# megapci3.net
KiCad netlist of a schematic drawn in EAGLE
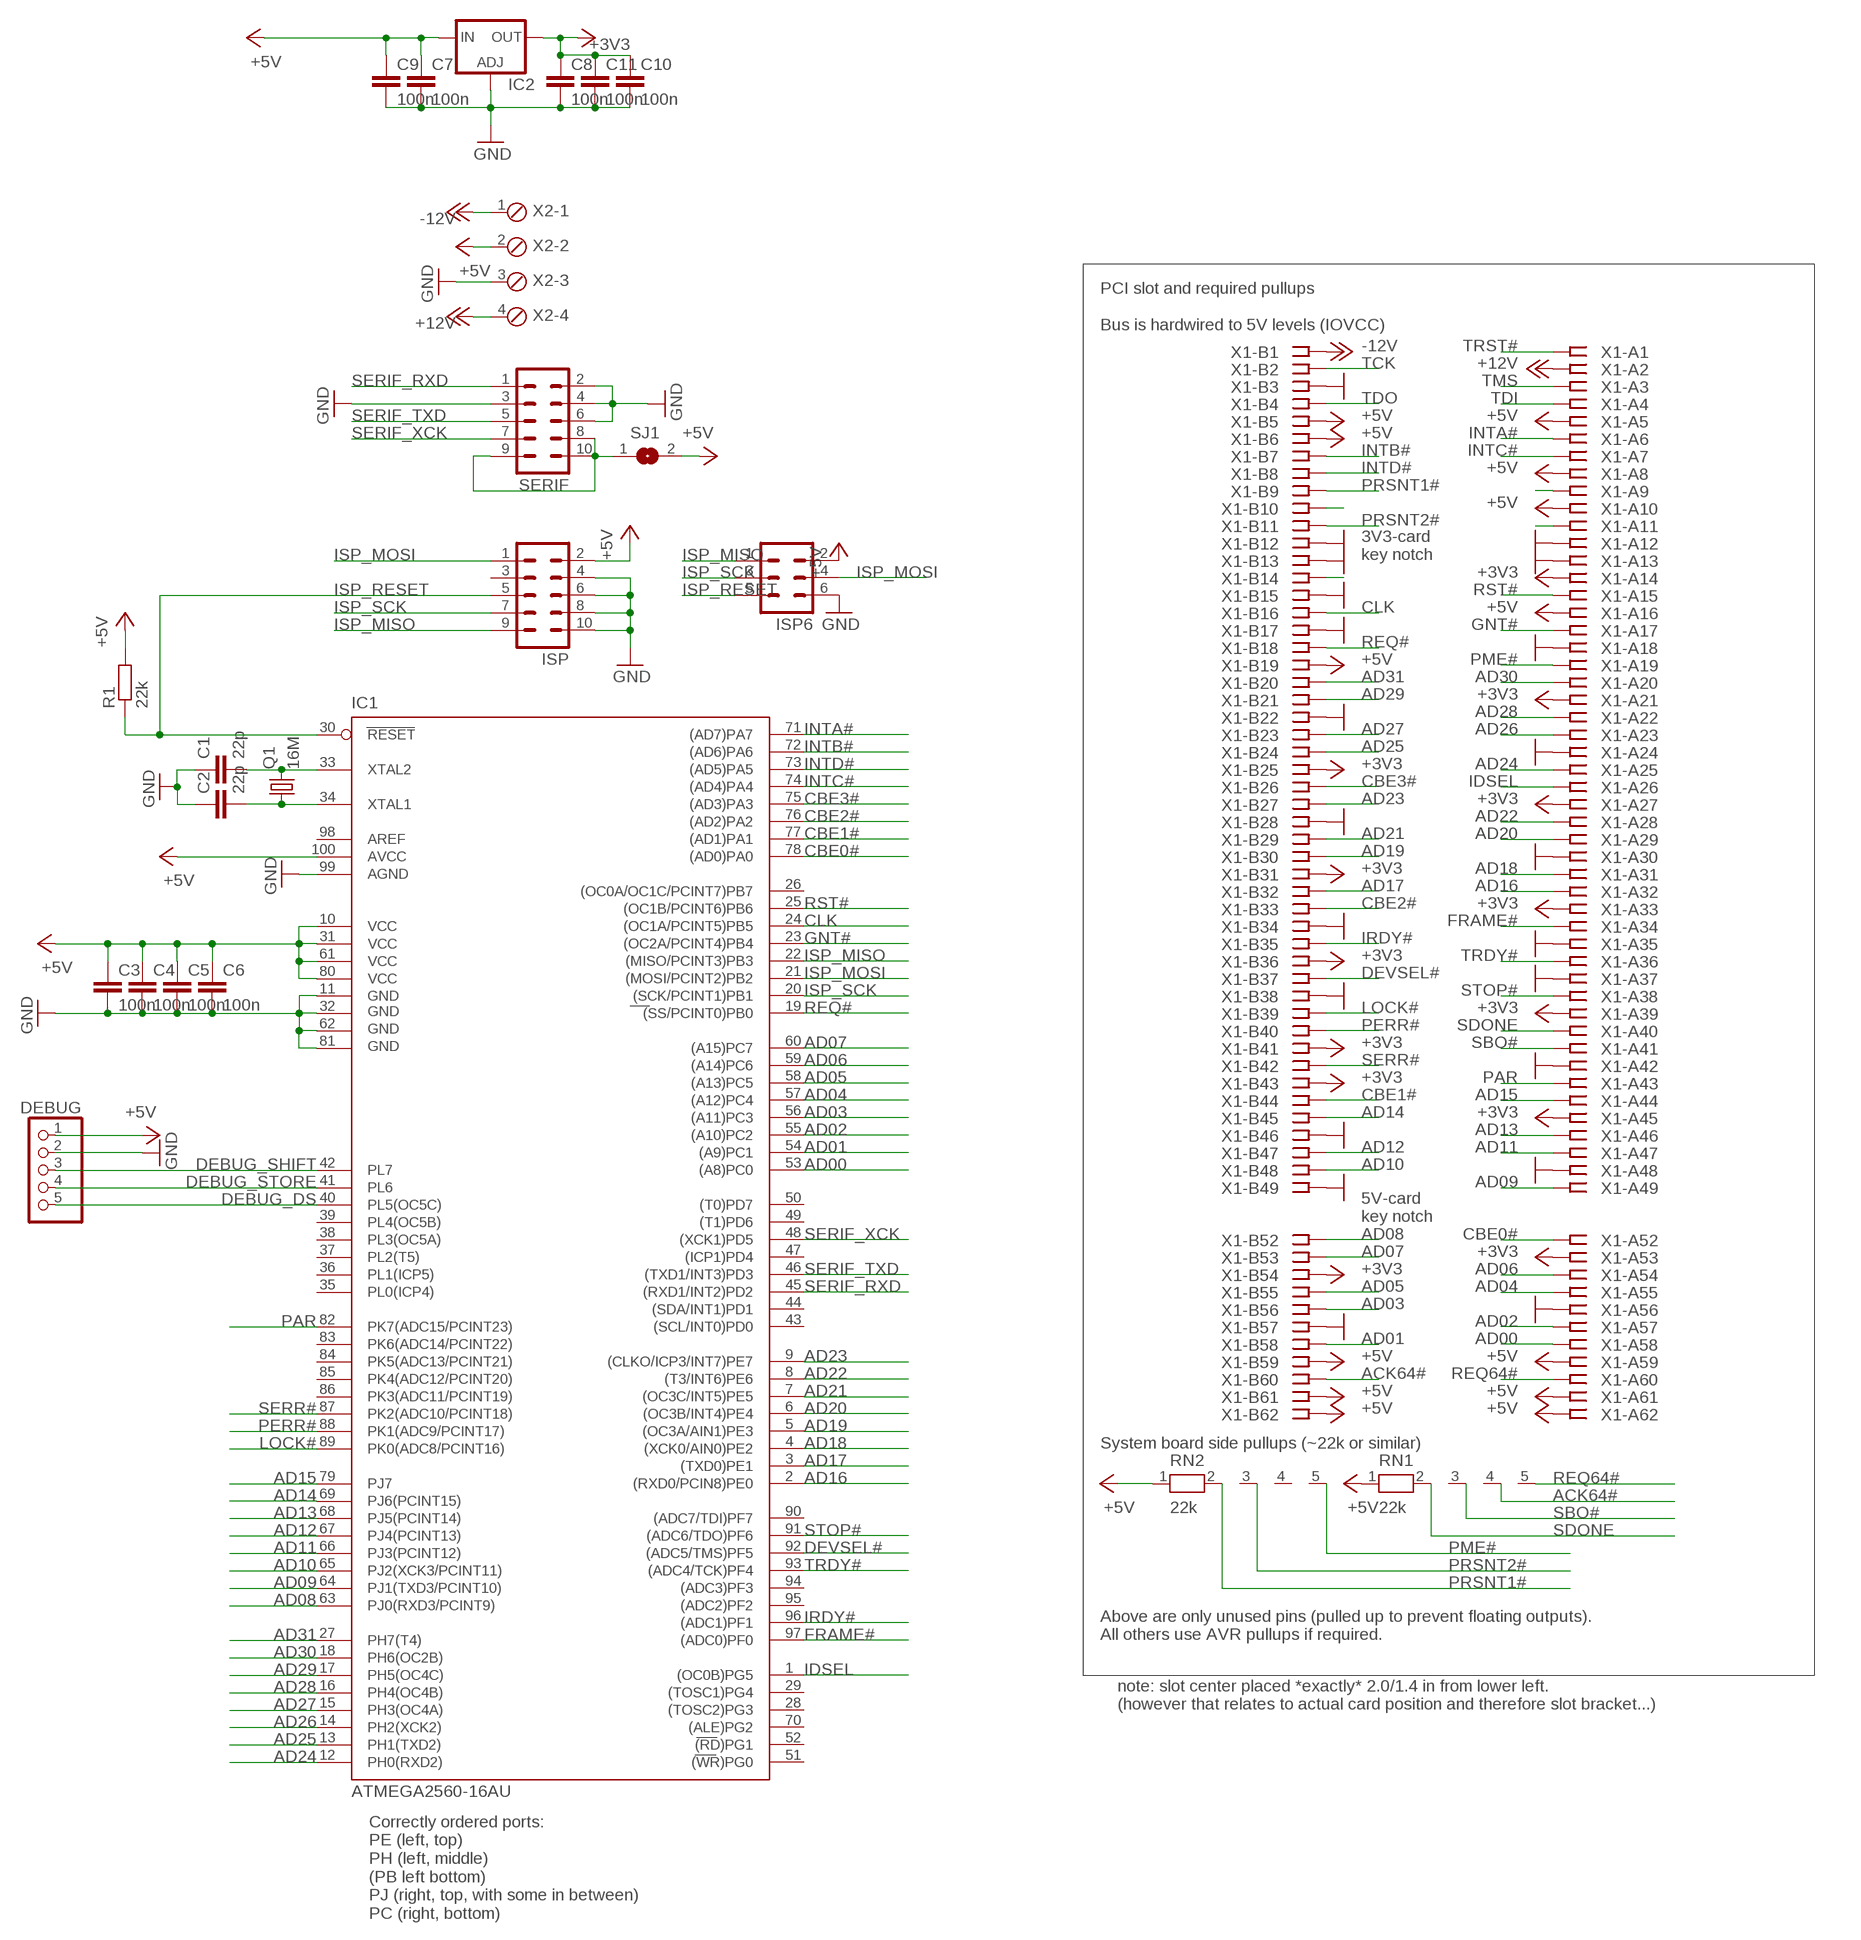
[diagram p0: schematic, sheet 1]

(export (version "E")
  (design (tool "Eeschema 10.0.6"))
  (components
    (comp (ref "C1")
      (value "22p")
      (footprint "eagle-import:C0805")
      (libsource (lib "eagle-import") (part "C-EUC0805"))
    )
    (comp (ref "C2")
      (value "22p")
      (footprint "eagle-import:C0805")
      (libsource (lib "eagle-import") (part "C-EUC0805"))
    )
    (comp (ref "C3")
      (value "100n")
      (footprint "eagle-import:C0805")
      (libsource (lib "eagle-import") (part "C-EUC0805"))
    )
    (comp (ref "C4")
      (value "100n")
      (footprint "eagle-import:C0805")
      (libsource (lib "eagle-import") (part "C-EUC0805"))
    )
    (comp (ref "C5")
      (value "100n")
      (footprint "eagle-import:C0805")
      (libsource (lib "eagle-import") (part "C-EUC0805"))
    )
    (comp (ref "C6")
      (value "100n")
      (footprint "eagle-import:C0805")
      (libsource (lib "eagle-import") (part "C-EUC0805"))
    )
    (comp (ref "C7")
      (value "100n")
      (footprint "eagle-import:C0805")
      (libsource (lib "eagle-import") (part "C-EUC0805"))
    )
    (comp (ref "C8")
      (value "100n")
      (footprint "eagle-import:C0805")
      (libsource (lib "eagle-import") (part "C-EUC0805"))
    )
    (comp (ref "C9")
      (value "100n")
      (footprint "eagle-import:C0805")
      (libsource (lib "eagle-import") (part "C-EUC0805"))
    )
    (comp (ref "C10")
      (value "100n")
      (footprint "eagle-import:C0805")
      (libsource (lib "eagle-import") (part "C-EUC0805"))
    )
    (comp (ref "C11")
      (value "100n")
      (footprint "eagle-import:C0805")
      (libsource (lib "eagle-import") (part "C-EUC0805"))
    )
    (comp (ref "DEBUG")
      (value "PINHD-1X5")
      (footprint "eagle-import:1X05")
      (libsource (lib "eagle-import") (part "PINHD-1X5"))
    )
    (comp (ref "IC1")
      (value "ATMEGA2560-16AU")
      (footprint "eagle-import:TQFP100")
      (libsource (lib "eagle-import") (part "ATMEGAAU2560-16"))
    )
    (comp (ref "IC2")
      (value "LM317TS")
      (footprint "eagle-import:317TS")
      (libsource (lib "eagle-import") (part "LM317TS"))
    )
    (comp (ref "ISP")
      (value "ML10")
      (footprint "eagle-import:ML10")
      (libsource (lib "eagle-import") (part "ML10"))
    )
    (comp (ref "ISP6")
      (value "ML6")
      (footprint "eagle-import:ML6")
      (libsource (lib "eagle-import") (part "ML6"))
    )
    (comp (ref "Q1")
      (value "16M")
      (footprint "eagle-import:HC49_S")
      (libsource (lib "eagle-import") (part "CRYSTALHC49S"))
    )
    (comp (ref "R1")
      (value "22k")
      (footprint "eagle-import:R0805")
      (libsource (lib "eagle-import") (part "R-EU_R0805"))
    )
    (comp (ref "RN1")
      (value "22k")
      (footprint "eagle-import:RN-5")
      (libsource (lib "eagle-import") (part "RN04"))
    )
    (comp (ref "RN2")
      (value "22k")
      (footprint "eagle-import:RN-5")
      (libsource (lib "eagle-import") (part "RN04"))
    )
    (comp (ref "SERIF")
      (value "ML10")
      (footprint "eagle-import:ML10")
      (libsource (lib "eagle-import") (part "ML10"))
    )
    (comp (ref "SJ1") (value "SJ") (footprint "eagle-import:SJ") (libsource (lib "eagle-import") (part "SJ")))
    (comp (ref "X1")
      (value "PCI-SLOT")
      (footprint "eagle-import:CON-PCI")
      (libsource (lib "eagle-import") (part "PCI-SLOT"))
    )
    (comp (ref "X2")
      (value "MPT4")
      (footprint "eagle-import:4POL254")
      (libsource (lib "eagle-import") (part "MPT4"))
    )
  )
  (nets
    (net (code "1") (name "+3V3") (class "Default")
      (node (ref "C10") (pin "1") (pinfunction "1_1") (pintype "passive"))
      (node (ref "C11") (pin "1") (pinfunction "1_1") (pintype "passive"))
      (node (ref "C8") (pin "1") (pinfunction "1_1") (pintype "passive"))
      (node (ref "IC2") (pin "2") (pinfunction "OUT_2") (pintype "passive"))
      (node (ref "X1") (pin "A14") (pinfunction "P_A14") (pintype "passive"))
      (node (ref "X1") (pin "A21") (pinfunction "P_A21") (pintype "passive"))
      (node (ref "X1") (pin "A27") (pinfunction "P_A27") (pintype "passive"))
      (node (ref "X1") (pin "A33") (pinfunction "P_A33") (pintype "passive"))
      (node (ref "X1") (pin "A39") (pinfunction "P_A39") (pintype "passive"))
      (node (ref "X1") (pin "A45") (pinfunction "P_A45") (pintype "passive"))
      (node (ref "X1") (pin "A53") (pinfunction "P_A53") (pintype "passive"))
      (node (ref "X1") (pin "B25") (pinfunction "P_B25") (pintype "passive"))
      (node (ref "X1") (pin "B31") (pinfunction "P_B31") (pintype "passive"))
      (node (ref "X1") (pin "B36") (pinfunction "P_B36") (pintype "passive"))
      (node (ref "X1") (pin "B41") (pinfunction "P_B41") (pintype "passive"))
      (node (ref "X1") (pin "B43") (pinfunction "P_B43") (pintype "passive"))
      (node (ref "X1") (pin "B54") (pinfunction "P_B54") (pintype "passive"))
    )
    (net (code "2") (name "+5V") (class "Default")
      (node (ref "C3") (pin "1") (pinfunction "1_1") (pintype "passive"))
      (node (ref "C4") (pin "1") (pinfunction "1_1") (pintype "passive"))
      (node (ref "C5") (pin "1") (pinfunction "1_1") (pintype "passive"))
      (node (ref "C6") (pin "1") (pinfunction "1_1") (pintype "passive"))
      (node (ref "C7") (pin "1") (pinfunction "1_1") (pintype "passive"))
      (node (ref "C9") (pin "1") (pinfunction "1_1") (pintype "passive"))
      (node (ref "DEBUG") (pin "1") (pinfunction "1_1") (pintype "passive"))
      (node (ref "IC1") (pin "10") (pinfunction "VCC_10") (pintype "power_in"))
      (node (ref "IC1") (pin "100") (pinfunction "AVCC_100") (pintype "power_in"))
      (node (ref "IC1") (pin "31") (pinfunction "VCC1_31") (pintype "power_in"))
      (node (ref "IC1") (pin "61") (pinfunction "VCC2_61") (pintype "power_in"))
      (node (ref "IC1") (pin "80") (pinfunction "VCC3_80") (pintype "power_in"))
      (node (ref "IC2") (pin "3") (pinfunction "IN_3") (pintype "input"))
      (node (ref "ISP") (pin "2") (pinfunction "2_2") (pintype "passive"))
      (node (ref "ISP6") (pin "2") (pinfunction "2_2") (pintype "passive"))
      (node (ref "R1") (pin "2") (pinfunction "2_2") (pintype "passive"))
      (node (ref "RN1") (pin "1") (pinfunction "1_1") (pintype "passive"))
      (node (ref "RN2") (pin "1") (pinfunction "1_1") (pintype "passive"))
      (node (ref "SJ1") (pin "2") (pinfunction "2_2") (pintype "passive"))
      (node (ref "X1") (pin "A10") (pinfunction "P_A10") (pintype "passive"))
      (node (ref "X1") (pin "A16") (pinfunction "P_A16") (pintype "passive"))
      (node (ref "X1") (pin "A5") (pinfunction "P_A5") (pintype "passive"))
      (node (ref "X1") (pin "A59") (pinfunction "P_A59") (pintype "passive"))
      (node (ref "X1") (pin "A61") (pinfunction "P_A61") (pintype "passive"))
      (node (ref "X1") (pin "A62") (pinfunction "P_A62") (pintype "passive"))
      (node (ref "X1") (pin "A8") (pinfunction "P_A8") (pintype "passive"))
      (node (ref "X1") (pin "B19") (pinfunction "P_B19") (pintype "passive"))
      (node (ref "X1") (pin "B5") (pinfunction "P_B5") (pintype "passive"))
      (node (ref "X1") (pin "B59") (pinfunction "P_B59") (pintype "passive"))
      (node (ref "X1") (pin "B6") (pinfunction "P_B6") (pintype "passive"))
      (node (ref "X1") (pin "B61") (pinfunction "P_B61") (pintype "passive"))
      (node (ref "X1") (pin "B62") (pinfunction "P_B62") (pintype "passive"))
      (node (ref "X2") (pin "2") (pinfunction "1_2") (pintype "passive"))
    )
    (net (code "3") (name "+12V") (class "Default")
      (node (ref "X1") (pin "A2") (pinfunction "P_A2") (pintype "passive"))
      (node (ref "X2") (pin "4") (pinfunction "1_4") (pintype "passive"))
    )
    (net (code "4") (name "-12V") (class "Default")
      (node (ref "X1") (pin "B1") (pinfunction "P_B1") (pintype "passive"))
      (node (ref "X2") (pin "1") (pinfunction "1_1") (pintype "passive"))
    )
    (net (code "5") (name "/ACK64#") (class "Default")
      (node (ref "RN1") (pin "4") (pinfunction "4_4") (pintype "passive"))
      (node (ref "X1") (pin "B60") (pinfunction "P_B60") (pintype "passive"))
    )
    (net (code "6") (name "/AD00") (class "Default")
      (node (ref "IC1") (pin "53") (pinfunction "(A8)PC0_53") (pintype "bidirectional"))
      (node (ref "X1") (pin "A58") (pinfunction "P_A58") (pintype "passive"))
    )
    (net (code "7") (name "/AD01") (class "Default")
      (node (ref "IC1") (pin "54") (pinfunction "(A9)PC1_54") (pintype "bidirectional"))
      (node (ref "X1") (pin "B58") (pinfunction "P_B58") (pintype "passive"))
    )
    (net (code "8") (name "/AD02") (class "Default")
      (node (ref "IC1") (pin "55") (pinfunction "(A10)PC2_55") (pintype "bidirectional"))
      (node (ref "X1") (pin "A57") (pinfunction "P_A57") (pintype "passive"))
    )
    (net (code "9") (name "/AD03") (class "Default")
      (node (ref "IC1") (pin "56") (pinfunction "(A11)PC3_56") (pintype "bidirectional"))
      (node (ref "X1") (pin "B56") (pinfunction "P_B56") (pintype "passive"))
    )
    (net (code "10") (name "/AD04") (class "Default")
      (node (ref "IC1") (pin "57") (pinfunction "(A12)PC4_57") (pintype "bidirectional"))
      (node (ref "X1") (pin "A55") (pinfunction "P_A55") (pintype "passive"))
    )
    (net (code "11") (name "/AD05") (class "Default")
      (node (ref "IC1") (pin "58") (pinfunction "(A13)PC5_58") (pintype "bidirectional"))
      (node (ref "X1") (pin "B55") (pinfunction "P_B55") (pintype "passive"))
    )
    (net (code "12") (name "/AD06") (class "Default")
      (node (ref "IC1") (pin "59") (pinfunction "(A14)PC6_59") (pintype "bidirectional"))
      (node (ref "X1") (pin "A54") (pinfunction "P_A54") (pintype "passive"))
    )
    (net (code "13") (name "/AD07") (class "Default")
      (node (ref "IC1") (pin "60") (pinfunction "(A15)PC7_60") (pintype "bidirectional"))
      (node (ref "X1") (pin "B53") (pinfunction "P_B53") (pintype "passive"))
    )
    (net (code "14") (name "/AD08") (class "Default")
      (node (ref "IC1") (pin "63") (pinfunction "PJ0(RXD3/PCINT9)_63") (pintype "bidirectional"))
      (node (ref "X1") (pin "B52") (pinfunction "P_B52") (pintype "passive"))
    )
    (net (code "15") (name "/AD09") (class "Default")
      (node (ref "IC1") (pin "64") (pinfunction "PJ1(TXD3/PCINT10)_64") (pintype "bidirectional"))
      (node (ref "X1") (pin "A49") (pinfunction "P_A49") (pintype "passive"))
    )
    (net (code "16") (name "/AD10") (class "Default")
      (node (ref "IC1") (pin "65") (pinfunction "PJ2(XCK3/PCINT11)_65") (pintype "bidirectional"))
      (node (ref "X1") (pin "B48") (pinfunction "P_B48") (pintype "passive"))
    )
    (net (code "17") (name "/AD11") (class "Default")
      (node (ref "IC1") (pin "66") (pinfunction "PJ3(PCINT12)_66") (pintype "bidirectional"))
      (node (ref "X1") (pin "A47") (pinfunction "P_A47") (pintype "passive"))
    )
    (net (code "18") (name "/AD12") (class "Default")
      (node (ref "IC1") (pin "67") (pinfunction "PJ4(PCINT13)_67") (pintype "bidirectional"))
      (node (ref "X1") (pin "B47") (pinfunction "P_B47") (pintype "passive"))
    )
    (net (code "19") (name "/AD13") (class "Default")
      (node (ref "IC1") (pin "68") (pinfunction "PJ5(PCINT14)_68") (pintype "bidirectional"))
      (node (ref "X1") (pin "A46") (pinfunction "P_A46") (pintype "passive"))
    )
    (net (code "20") (name "/AD14") (class "Default")
      (node (ref "IC1") (pin "69") (pinfunction "PJ6(PCINT15)_69") (pintype "bidirectional"))
      (node (ref "X1") (pin "B45") (pinfunction "P_B45") (pintype "passive"))
    )
    (net (code "21") (name "/AD15") (class "Default")
      (node (ref "IC1") (pin "79") (pinfunction "PJ7_79") (pintype "bidirectional"))
      (node (ref "X1") (pin "A44") (pinfunction "P_A44") (pintype "passive"))
    )
    (net (code "22") (name "/AD16") (class "Default")
      (node (ref "IC1") (pin "2") (pinfunction "(RXD0/PCIN8)PE0_2") (pintype "bidirectional"))
      (node (ref "X1") (pin "A32") (pinfunction "P_A32") (pintype "passive"))
    )
    (net (code "23") (name "/AD17") (class "Default")
      (node (ref "IC1") (pin "3") (pinfunction "(TXD0)PE1_3") (pintype "bidirectional"))
      (node (ref "X1") (pin "B32") (pinfunction "P_B32") (pintype "passive"))
    )
    (net (code "24") (name "/AD18") (class "Default")
      (node (ref "IC1") (pin "4") (pinfunction "(XCK0/AIN0)PE2_4") (pintype "bidirectional"))
      (node (ref "X1") (pin "A31") (pinfunction "P_A31") (pintype "passive"))
    )
    (net (code "25") (name "/AD19") (class "Default")
      (node (ref "IC1") (pin "5") (pinfunction "(OC3A/AIN1)PE3_5") (pintype "bidirectional"))
      (node (ref "X1") (pin "B30") (pinfunction "P_B30") (pintype "passive"))
    )
    (net (code "26") (name "/AD20") (class "Default")
      (node (ref "IC1") (pin "6") (pinfunction "(OC3B/INT4)PE4_6") (pintype "bidirectional"))
      (node (ref "X1") (pin "A29") (pinfunction "P_A29") (pintype "passive"))
    )
    (net (code "27") (name "/AD21") (class "Default")
      (node (ref "IC1") (pin "7") (pinfunction "(OC3C/INT5)PE5_7") (pintype "bidirectional"))
      (node (ref "X1") (pin "B29") (pinfunction "P_B29") (pintype "passive"))
    )
    (net (code "28") (name "/AD22") (class "Default")
      (node (ref "IC1") (pin "8") (pinfunction "(T3/INT6)PE6_8") (pintype "bidirectional"))
      (node (ref "X1") (pin "A28") (pinfunction "P_A28") (pintype "passive"))
    )
    (net (code "29") (name "/AD23") (class "Default")
      (node (ref "IC1") (pin "9") (pinfunction "(CLKO/ICP3/INT7)PE7_9") (pintype "bidirectional"))
      (node (ref "X1") (pin "B27") (pinfunction "P_B27") (pintype "passive"))
    )
    (net (code "30") (name "/AD24") (class "Default")
      (node (ref "IC1") (pin "12") (pinfunction "PH0(RXD2)_12") (pintype "bidirectional"))
      (node (ref "X1") (pin "A25") (pinfunction "P_A25") (pintype "passive"))
    )
    (net (code "31") (name "/AD25") (class "Default")
      (node (ref "IC1") (pin "13") (pinfunction "PH1(TXD2)_13") (pintype "bidirectional"))
      (node (ref "X1") (pin "B24") (pinfunction "P_B24") (pintype "passive"))
    )
    (net (code "32") (name "/AD26") (class "Default")
      (node (ref "IC1") (pin "14") (pinfunction "PH2(XCK2)_14") (pintype "bidirectional"))
      (node (ref "X1") (pin "A23") (pinfunction "P_A23") (pintype "passive"))
    )
    (net (code "33") (name "/AD27") (class "Default")
      (node (ref "IC1") (pin "15") (pinfunction "PH3(OC4A)_15") (pintype "bidirectional"))
      (node (ref "X1") (pin "B23") (pinfunction "P_B23") (pintype "passive"))
    )
    (net (code "34") (name "/AD28") (class "Default")
      (node (ref "IC1") (pin "16") (pinfunction "PH4(OC4B)_16") (pintype "bidirectional"))
      (node (ref "X1") (pin "A22") (pinfunction "P_A22") (pintype "passive"))
    )
    (net (code "35") (name "/AD29") (class "Default")
      (node (ref "IC1") (pin "17") (pinfunction "PH5(OC4C)_17") (pintype "bidirectional"))
      (node (ref "X1") (pin "B21") (pinfunction "P_B21") (pintype "passive"))
    )
    (net (code "36") (name "/AD30") (class "Default")
      (node (ref "IC1") (pin "18") (pinfunction "PH6(OC2B)_18") (pintype "bidirectional"))
      (node (ref "X1") (pin "A20") (pinfunction "P_A20") (pintype "passive"))
    )
    (net (code "37") (name "/AD31") (class "Default")
      (node (ref "IC1") (pin "27") (pinfunction "PH7(T4)_27") (pintype "bidirectional"))
      (node (ref "X1") (pin "B20") (pinfunction "P_B20") (pintype "passive"))
    )
    (net (code "38") (name "/CBE0#") (class "Default")
      (node (ref "IC1") (pin "78") (pinfunction "(AD0)PA0_78") (pintype "bidirectional"))
      (node (ref "X1") (pin "A52") (pinfunction "P_A52") (pintype "passive"))
    )
    (net (code "39") (name "/CBE1#") (class "Default")
      (node (ref "IC1") (pin "77") (pinfunction "(AD1)PA1_77") (pintype "bidirectional"))
      (node (ref "X1") (pin "B44") (pinfunction "P_B44") (pintype "passive"))
    )
    (net (code "40") (name "/CBE2#") (class "Default")
      (node (ref "IC1") (pin "76") (pinfunction "(AD2)PA2_76") (pintype "bidirectional"))
      (node (ref "X1") (pin "B33") (pinfunction "P_B33") (pintype "passive"))
    )
    (net (code "41") (name "/CBE3#") (class "Default")
      (node (ref "IC1") (pin "75") (pinfunction "(AD3)PA3_75") (pintype "bidirectional"))
      (node (ref "X1") (pin "B26") (pinfunction "P_B26") (pintype "passive"))
    )
    (net (code "42") (name "/CLK") (class "Default")
      (node (ref "IC1") (pin "24") (pinfunction "(OC1A/PCINT5)PB5_24") (pintype "bidirectional"))
      (node (ref "X1") (pin "B16") (pinfunction "P_B16") (pintype "passive"))
    )
    (net (code "43") (name "/DEBUG_DS") (class "Default")
      (node (ref "DEBUG") (pin "5") (pinfunction "5_5") (pintype "passive"))
      (node (ref "IC1") (pin "40") (pinfunction "PL5(OC5C)_40") (pintype "bidirectional"))
    )
    (net (code "44") (name "/DEBUG_SHIFT") (class "Default")
      (node (ref "DEBUG") (pin "3") (pinfunction "3_3") (pintype "passive"))
      (node (ref "IC1") (pin "42") (pinfunction "PL7_42") (pintype "bidirectional"))
    )
    (net (code "45") (name "/DEBUG_STORE") (class "Default")
      (node (ref "DEBUG") (pin "4") (pinfunction "4_4") (pintype "passive"))
      (node (ref "IC1") (pin "41") (pinfunction "PL6_41") (pintype "bidirectional"))
    )
    (net (code "46") (name "/DEVSEL#") (class "Default")
      (node (ref "IC1") (pin "92") (pinfunction "(ADC5/TMS)PF5_92") (pintype "bidirectional"))
      (node (ref "X1") (pin "B37") (pinfunction "P_B37") (pintype "passive"))
    )
    (net (code "47") (name "/FRAME#") (class "Default")
      (node (ref "IC1") (pin "97") (pinfunction "(ADC0)PF0_97") (pintype "bidirectional"))
      (node (ref "X1") (pin "A34") (pinfunction "P_A34") (pintype "passive"))
    )
    (net (code "48") (name "/GNT#") (class "Default")
      (node (ref "IC1") (pin "23") (pinfunction "(OC2A/PCINT4)PB4_23") (pintype "bidirectional"))
      (node (ref "X1") (pin "A17") (pinfunction "P_A17") (pintype "passive"))
    )
    (net (code "49") (name "/IDSEL") (class "Default")
      (node (ref "IC1") (pin "1") (pinfunction "(OC0B)PG5_1") (pintype "bidirectional"))
      (node (ref "X1") (pin "A26") (pinfunction "P_A26") (pintype "passive"))
    )
    (net (code "50") (name "/INTA#") (class "Default")
      (node (ref "IC1") (pin "71") (pinfunction "(AD7)PA7_71") (pintype "bidirectional"))
      (node (ref "X1") (pin "A6") (pinfunction "P_A6") (pintype "passive"))
    )
    (net (code "51") (name "/INTB#") (class "Default")
      (node (ref "IC1") (pin "72") (pinfunction "(AD6)PA6_72") (pintype "bidirectional"))
      (node (ref "X1") (pin "B7") (pinfunction "P_B7") (pintype "passive"))
    )
    (net (code "52") (name "/INTC#") (class "Default")
      (node (ref "IC1") (pin "74") (pinfunction "(AD4)PA4_74") (pintype "bidirectional"))
      (node (ref "X1") (pin "A7") (pinfunction "P_A7") (pintype "passive"))
    )
    (net (code "53") (name "/INTD#") (class "Default")
      (node (ref "IC1") (pin "73") (pinfunction "(AD5)PA5_73") (pintype "bidirectional"))
      (node (ref "X1") (pin "B8") (pinfunction "P_B8") (pintype "passive"))
    )
    (net (code "54") (name "/IRDY#") (class "Default")
      (node (ref "IC1") (pin "96") (pinfunction "(ADC1)PF1_96") (pintype "bidirectional"))
      (node (ref "X1") (pin "B35") (pinfunction "P_B35") (pintype "passive"))
    )
    (net (code "55") (name "/ISP_MISO") (class "Default")
      (node (ref "IC1") (pin "22") (pinfunction "(MISO/PCINT3)PB3_22") (pintype "bidirectional"))
      (node (ref "ISP") (pin "9") (pinfunction "9_9") (pintype "passive"))
      (node (ref "ISP6") (pin "1") (pinfunction "1_1") (pintype "passive"))
    )
    (net (code "56") (name "/ISP_MOSI") (class "Default")
      (node (ref "IC1") (pin "21") (pinfunction "(MOSI/PCINT2)PB2_21") (pintype "bidirectional"))
      (node (ref "ISP") (pin "1") (pinfunction "1_1") (pintype "passive"))
      (node (ref "ISP6") (pin "4") (pinfunction "4_4") (pintype "passive"))
    )
    (net (code "57") (name "/ISP_RESET") (class "Default")
      (node (ref "IC1") (pin "30") (pinfunction "RESET_30") (pintype "input"))
      (node (ref "ISP") (pin "5") (pinfunction "5_5") (pintype "passive"))
      (node (ref "ISP6") (pin "5") (pinfunction "5_5") (pintype "passive"))
      (node (ref "R1") (pin "1") (pinfunction "1_1") (pintype "passive"))
    )
    (net (code "58") (name "/ISP_SCK") (class "Default")
      (node (ref "IC1") (pin "20") (pinfunction "(SCK/PCINT1)PB1_20") (pintype "bidirectional"))
      (node (ref "ISP") (pin "7") (pinfunction "7_7") (pintype "passive"))
      (node (ref "ISP6") (pin "3") (pinfunction "3_3") (pintype "passive"))
    )
    (net (code "59") (name "/LOCK#") (class "Default")
      (node (ref "IC1") (pin "89") (pinfunction "PK0(ADC8/PCINT16)_89") (pintype "bidirectional"))
      (node (ref "X1") (pin "B39") (pinfunction "P_B39") (pintype "passive"))
    )
    (net (code "60") (name "/PAR") (class "Default")
      (node (ref "IC1") (pin "82") (pinfunction "PK7(ADC15/PCINT23)_82") (pintype "bidirectional"))
      (node (ref "X1") (pin "A43") (pinfunction "P_A43") (pintype "passive"))
    )
    (net (code "61") (name "/PERR#") (class "Default")
      (node (ref "IC1") (pin "88") (pinfunction "PK1(ADC9/PCINT17)_88") (pintype "bidirectional"))
      (node (ref "X1") (pin "B40") (pinfunction "P_B40") (pintype "passive"))
    )
    (net (code "62") (name "/PME#") (class "Default")
      (node (ref "RN2") (pin "5") (pinfunction "5_5") (pintype "passive"))
      (node (ref "X1") (pin "A19") (pinfunction "P_A19") (pintype "passive"))
    )
    (net (code "63") (name "/PRSNT1#") (class "Default")
      (node (ref "RN2") (pin "2") (pinfunction "2_2") (pintype "passive"))
      (node (ref "X1") (pin "B9") (pinfunction "P_B9") (pintype "passive"))
    )
    (net (code "64") (name "/PRSNT2#") (class "Default")
      (node (ref "RN2") (pin "3") (pinfunction "3_3") (pintype "passive"))
      (node (ref "X1") (pin "B11") (pinfunction "P_B11") (pintype "passive"))
    )
    (net (code "65") (name "/REQ#") (class "Default")
      (node (ref "IC1") (pin "19") (pinfunction "(SS/PCINT0)PB0_19") (pintype "bidirectional"))
      (node (ref "X1") (pin "B18") (pinfunction "P_B18") (pintype "passive"))
    )
    (net (code "66") (name "/REQ64#") (class "Default")
      (node (ref "RN1") (pin "5") (pinfunction "5_5") (pintype "passive"))
      (node (ref "X1") (pin "A60") (pinfunction "P_A60") (pintype "passive"))
    )
    (net (code "67") (name "/RST#") (class "Default")
      (node (ref "IC1") (pin "25") (pinfunction "(OC1B/PCINT6)PB6_25") (pintype "bidirectional"))
      (node (ref "X1") (pin "A15") (pinfunction "P_A15") (pintype "passive"))
    )
    (net (code "68") (name "/SBO#") (class "Default")
      (node (ref "RN1") (pin "3") (pinfunction "3_3") (pintype "passive"))
      (node (ref "X1") (pin "A41") (pinfunction "P_A41") (pintype "passive"))
    )
    (net (code "69") (name "/SDONE") (class "Default")
      (node (ref "RN1") (pin "2") (pinfunction "2_2") (pintype "passive"))
      (node (ref "X1") (pin "A40") (pinfunction "P_A40") (pintype "passive"))
    )
    (net (code "70") (name "/SERIF_RXD") (class "Default")
      (node (ref "IC1") (pin "45") (pinfunction "(RXD1/INT2)PD2_45") (pintype "bidirectional"))
      (node (ref "SERIF") (pin "1") (pinfunction "1_1") (pintype "passive"))
    )
    (net (code "71") (name "/SERIF_TXD") (class "Default")
      (node (ref "IC1") (pin "46") (pinfunction "(TXD1/INT3)PD3_46") (pintype "bidirectional"))
      (node (ref "SERIF") (pin "5") (pinfunction "5_5") (pintype "passive"))
    )
    (net (code "72") (name "/SERIF_XCK") (class "Default")
      (node (ref "IC1") (pin "48") (pinfunction "(XCK1)PD5_48") (pintype "bidirectional"))
      (node (ref "SERIF") (pin "7") (pinfunction "7_7") (pintype "passive"))
    )
    (net (code "73") (name "/SERR#") (class "Default")
      (node (ref "IC1") (pin "87") (pinfunction "PK2(ADC10/PCINT18)_87") (pintype "bidirectional"))
      (node (ref "X1") (pin "B42") (pinfunction "P_B42") (pintype "passive"))
    )
    (net (code "74") (name "/STOP#") (class "Default")
      (node (ref "IC1") (pin "91") (pinfunction "(ADC6/TDO)PF6_91") (pintype "bidirectional"))
      (node (ref "X1") (pin "A38") (pinfunction "P_A38") (pintype "passive"))
    )
    (net (code "75") (name "/TCK") (class "Default")
      (node (ref "X1") (pin "B2") (pinfunction "P_B2") (pintype "passive"))
    )
    (net (code "76") (name "/TDI") (class "Default")
      (node (ref "X1") (pin "A4") (pinfunction "P_A4") (pintype "passive"))
    )
    (net (code "77") (name "/TDO") (class "Default")
      (node (ref "X1") (pin "B4") (pinfunction "P_B4") (pintype "passive"))
    )
    (net (code "78") (name "/TMS") (class "Default")
      (node (ref "X1") (pin "A3") (pinfunction "P_A3") (pintype "passive"))
    )
    (net (code "79") (name "/TRDY#") (class "Default")
      (node (ref "IC1") (pin "93") (pinfunction "(ADC4/TCK)PF4_93") (pintype "bidirectional"))
      (node (ref "X1") (pin "A36") (pinfunction "P_A36") (pintype "passive"))
    )
    (net (code "80") (name "/TRST#") (class "Default")
      (node (ref "X1") (pin "A1") (pinfunction "P_A1") (pintype "passive"))
    )
    (net (code "81") (name "GND") (class "Default")
      (node (ref "C1") (pin "1") (pinfunction "1_1") (pintype "passive"))
      (node (ref "C10") (pin "2") (pinfunction "2_2") (pintype "passive"))
      (node (ref "C11") (pin "2") (pinfunction "2_2") (pintype "passive"))
      (node (ref "C2") (pin "1") (pinfunction "1_1") (pintype "passive"))
      (node (ref "C3") (pin "2") (pinfunction "2_2") (pintype "passive"))
      (node (ref "C4") (pin "2") (pinfunction "2_2") (pintype "passive"))
      (node (ref "C5") (pin "2") (pinfunction "2_2") (pintype "passive"))
      (node (ref "C6") (pin "2") (pinfunction "2_2") (pintype "passive"))
      (node (ref "C7") (pin "2") (pinfunction "2_2") (pintype "passive"))
      (node (ref "C8") (pin "2") (pinfunction "2_2") (pintype "passive"))
      (node (ref "C9") (pin "2") (pinfunction "2_2") (pintype "passive"))
      (node (ref "DEBUG") (pin "2") (pinfunction "2_2") (pintype "passive"))
      (node (ref "IC1") (pin "11") (pinfunction "GND_11") (pintype "power_in"))
      (node (ref "IC1") (pin "32") (pinfunction "GND1_32") (pintype "power_in"))
      (node (ref "IC1") (pin "62") (pinfunction "GND2_62") (pintype "power_in"))
      (node (ref "IC1") (pin "81") (pinfunction "GND3_81") (pintype "power_in"))
      (node (ref "IC1") (pin "99") (pinfunction "AGND_99") (pintype "power_in"))
      (node (ref "IC2") (pin "1") (pinfunction "ADJ_1") (pintype "input"))
      (node (ref "ISP") (pin "10") (pinfunction "10_10") (pintype "passive"))
      (node (ref "ISP") (pin "4") (pinfunction "4_4") (pintype "passive"))
      (node (ref "ISP") (pin "6") (pinfunction "6_6") (pintype "passive"))
      (node (ref "ISP") (pin "8") (pinfunction "8_8") (pintype "passive"))
      (node (ref "ISP6") (pin "6") (pinfunction "6_6") (pintype "passive"))
      (node (ref "SERIF") (pin "2") (pinfunction "2_2") (pintype "passive"))
      (node (ref "SERIF") (pin "3") (pinfunction "3_3") (pintype "passive"))
      (node (ref "SERIF") (pin "4") (pinfunction "4_4") (pintype "passive"))
      (node (ref "SERIF") (pin "6") (pinfunction "6_6") (pintype "passive"))
      (node (ref "X1") (pin "A12") (pinfunction "P_A12") (pintype "passive"))
      (node (ref "X1") (pin "A13") (pinfunction "P_A13") (pintype "passive"))
      (node (ref "X1") (pin "A18") (pinfunction "P_A18") (pintype "passive"))
      (node (ref "X1") (pin "A24") (pinfunction "P_A24") (pintype "passive"))
      (node (ref "X1") (pin "A30") (pinfunction "P_A30") (pintype "passive"))
      (node (ref "X1") (pin "A35") (pinfunction "P_A35") (pintype "passive"))
      (node (ref "X1") (pin "A37") (pinfunction "P_A37") (pintype "passive"))
      (node (ref "X1") (pin "A42") (pinfunction "P_A42") (pintype "passive"))
      (node (ref "X1") (pin "A48") (pinfunction "P_A48") (pintype "passive"))
      (node (ref "X1") (pin "A56") (pinfunction "P_A56") (pintype "passive"))
      (node (ref "X1") (pin "B12") (pinfunction "P_B12") (pintype "passive"))
      (node (ref "X1") (pin "B13") (pinfunction "P_B13") (pintype "passive"))
      (node (ref "X1") (pin "B15") (pinfunction "P_B15") (pintype "passive"))
      (node (ref "X1") (pin "B17") (pinfunction "P_B17") (pintype "passive"))
      (node (ref "X1") (pin "B22") (pinfunction "P_B22") (pintype "passive"))
      (node (ref "X1") (pin "B28") (pinfunction "P_B28") (pintype "passive"))
      (node (ref "X1") (pin "B3") (pinfunction "P_B3") (pintype "passive"))
      (node (ref "X1") (pin "B34") (pinfunction "P_B34") (pintype "passive"))
      (node (ref "X1") (pin "B38") (pinfunction "P_B38") (pintype "passive"))
      (node (ref "X1") (pin "B46") (pinfunction "P_B46") (pintype "passive"))
      (node (ref "X1") (pin "B49") (pinfunction "P_B49") (pintype "passive"))
      (node (ref "X1") (pin "B57") (pinfunction "P_B57") (pintype "passive"))
      (node (ref "X2") (pin "3") (pinfunction "1_3") (pintype "passive"))
    )
    (net (code "82") (name "Net-(IC1-XTAL1)") (class "Default")
      (node (ref "C2") (pin "2") (pinfunction "2_2") (pintype "passive"))
      (node (ref "IC1") (pin "34") (pinfunction "XTAL1_34") (pintype "input"))
      (node (ref "Q1") (pin "1") (pinfunction "1_1") (pintype "passive"))
    )
    (net (code "83") (name "Net-(IC1-XTAL2)") (class "Default")
      (node (ref "C1") (pin "2") (pinfunction "2_2") (pintype "passive"))
      (node (ref "IC1") (pin "33") (pinfunction "XTAL2_33") (pintype "output"))
      (node (ref "Q1") (pin "2") (pinfunction "2_2") (pintype "passive"))
    )
    (net (code "84") (name "Net-(SERIF-Pad10)") (class "Default")
      (node (ref "SERIF") (pin "10") (pinfunction "10_10") (pintype "passive"))
      (node (ref "SERIF") (pin "8") (pinfunction "8_8") (pintype "passive"))
      (node (ref "SERIF") (pin "9") (pinfunction "9_9") (pintype "passive"))
      (node (ref "SJ1") (pin "1") (pinfunction "1_1") (pintype "passive"))
    )
    (net (code "85") (name "unconnected-(IC1-(ADC2)PF2-Pad95)") (class "Default")
      (node (ref "IC1") (pin "95") (pinfunction "(ADC2)PF2_95") (pintype "bidirectional"))
    )
    (net (code "86") (name "unconnected-(IC1-(ADC3)PF3-Pad94)") (class "Default")
      (node (ref "IC1") (pin "94") (pinfunction "(ADC3)PF3_94") (pintype "bidirectional"))
    )
    (net (code "87") (name "unconnected-(IC1-(ADC7{slash}TDI)PF7-Pad90)") (class "Default")
      (node (ref "IC1") (pin "90") (pinfunction "(ADC7/TDI)PF7_90") (pintype "bidirectional"))
    )
    (net (code "88") (name "unconnected-(IC1-(ALE)PG2-Pad70)") (class "Default")
      (node (ref "IC1") (pin "70") (pinfunction "(ALE)PG2_70") (pintype "bidirectional"))
    )
    (net (code "89") (name "unconnected-(IC1-(ICP1)PD4-Pad47)") (class "Default")
      (node (ref "IC1") (pin "47") (pinfunction "(ICP1)PD4_47") (pintype "bidirectional"))
    )
    (net (code "90") (name "unconnected-(IC1-(OC0A{slash}OC1C{slash}PCINT7)PB7-Pad26)") (class "Default")
      (node (ref "IC1") (pin "26") (pinfunction "(OC0A/OC1C/PCINT7)PB7_26") (pintype "bidirectional"))
    )
    (net (code "91") (name "unconnected-(IC1-(RD)PG1-Pad52)") (class "Default")
      (node (ref "IC1") (pin "52") (pinfunction "(RD)PG1_52") (pintype "bidirectional"))
    )
    (net (code "92") (name "unconnected-(IC1-(SCL{slash}INT0)PD0-Pad43)") (class "Default")
      (node (ref "IC1") (pin "43") (pinfunction "(SCL/INT0)PD0_43") (pintype "bidirectional"))
    )
    (net (code "93") (name "unconnected-(IC1-(SDA{slash}INT1)PD1-Pad44)") (class "Default")
      (node (ref "IC1") (pin "44") (pinfunction "(SDA/INT1)PD1_44") (pintype "bidirectional"))
    )
    (net (code "94") (name "unconnected-(IC1-(T0)PD7-Pad50)") (class "Default")
      (node (ref "IC1") (pin "50") (pinfunction "(T0)PD7_50") (pintype "bidirectional"))
    )
    (net (code "95") (name "unconnected-(IC1-(T1)PD6-Pad49)") (class "Default")
      (node (ref "IC1") (pin "49") (pinfunction "(T1)PD6_49") (pintype "bidirectional"))
    )
    (net (code "96") (name "unconnected-(IC1-(TOSC1)PG4-Pad29)") (class "Default")
      (node (ref "IC1") (pin "29") (pinfunction "(TOSC1)PG4_29") (pintype "bidirectional"))
    )
    (net (code "97") (name "unconnected-(IC1-(TOSC2)PG3-Pad28)") (class "Default")
      (node (ref "IC1") (pin "28") (pinfunction "(TOSC2)PG3_28") (pintype "bidirectional"))
    )
    (net (code "98") (name "unconnected-(IC1-(WR)PG0-Pad51)") (class "Default")
      (node (ref "IC1") (pin "51") (pinfunction "(WR)PG0_51") (pintype "bidirectional"))
    )
    (net (code "99") (name "unconnected-(IC1-AREF-Pad98)") (class "Default")
      (node (ref "IC1") (pin "98") (pinfunction "AREF_98") (pintype "bidirectional"))
    )
    (net (code "100") (name "unconnected-(IC1-PK3(ADC11{slash}PCINT19)-Pad86)") (class "Default")
      (node (ref "IC1") (pin "86") (pinfunction "PK3(ADC11/PCINT19)_86") (pintype "bidirectional"))
    )
    (net (code "101") (name "unconnected-(IC1-PK4(ADC12{slash}PCINT20)-Pad85)") (class "Default")
      (node (ref "IC1") (pin "85") (pinfunction "PK4(ADC12/PCINT20)_85") (pintype "bidirectional"))
    )
    (net (code "102") (name "unconnected-(IC1-PK5(ADC13{slash}PCINT21)-Pad84)") (class "Default")
      (node (ref "IC1") (pin "84") (pinfunction "PK5(ADC13/PCINT21)_84") (pintype "bidirectional"))
    )
    (net (code "103") (name "unconnected-(IC1-PK6(ADC14{slash}PCINT22)-Pad83)") (class "Default")
      (node (ref "IC1") (pin "83") (pinfunction "PK6(ADC14/PCINT22)_83") (pintype "bidirectional"))
    )
    (net (code "104") (name "unconnected-(IC1-PL0(ICP4)-Pad35)") (class "Default")
      (node (ref "IC1") (pin "35") (pinfunction "PL0(ICP4)_35") (pintype "bidirectional"))
    )
    (net (code "105") (name "unconnected-(IC1-PL1(ICP5)-Pad36)") (class "Default")
      (node (ref "IC1") (pin "36") (pinfunction "PL1(ICP5)_36") (pintype "bidirectional"))
    )
    (net (code "106") (name "unconnected-(IC1-PL2(T5)-Pad37)") (class "Default")
      (node (ref "IC1") (pin "37") (pinfunction "PL2(T5)_37") (pintype "bidirectional"))
    )
    (net (code "107") (name "unconnected-(IC1-PL3(OC5A)-Pad38)") (class "Default")
      (node (ref "IC1") (pin "38") (pinfunction "PL3(OC5A)_38") (pintype "bidirectional"))
    )
    (net (code "108") (name "unconnected-(IC1-PL4(OC5B)-Pad39)") (class "Default")
      (node (ref "IC1") (pin "39") (pinfunction "PL4(OC5B)_39") (pintype "bidirectional"))
    )
    (net (code "109") (name "unconnected-(ISP-Pad3)") (class "Default")
      (node (ref "ISP") (pin "3") (pinfunction "3_3") (pintype "passive"))
    )
    (net (code "110") (name "unconnected-(RN2-Pad4)") (class "Default")
      (node (ref "RN2") (pin "4") (pinfunction "4_4") (pintype "passive"))
    )
    (net (code "111") (name "unconnected-(X1BH-P-PadA9)") (class "Default")
      (node (ref "X1") (pin "A9") (pinfunction "P_A9") (pintype "passive"))
    )
    (net (code "112") (name "unconnected-(X1BJ-P-PadB10)") (class "Default")
      (node (ref "X1") (pin "B10") (pinfunction "P_B10") (pintype "passive"))
    )
    (net (code "113") (name "unconnected-(X1BN-P-PadB14)") (class "Default")
      (node (ref "X1") (pin "B14") (pinfunction "P_B14") (pintype "passive"))
    )
    (net (code "114") (name "unconnected-(X1C-P-PadA11)") (class "Default")
      (node (ref "X1") (pin "A11") (pinfunction "P_A11") (pintype "passive"))
    )
  )
)
